# LEDcircuits_PWM.net
KiCad netlist of a schematic drawn in Altium Designer
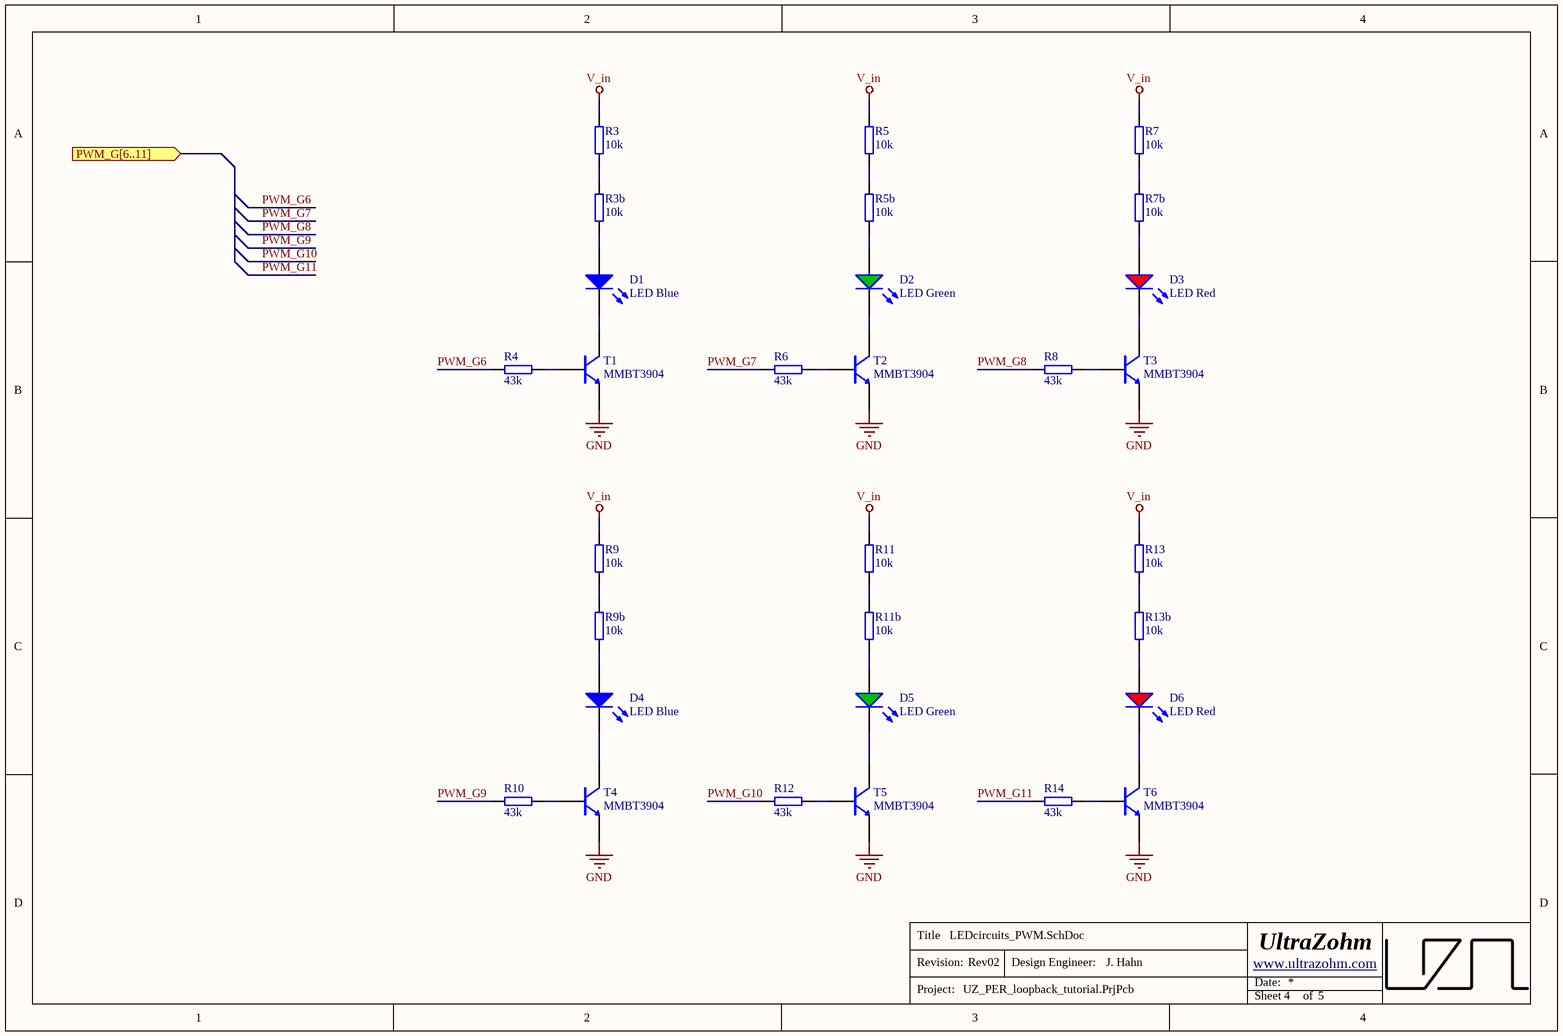
[diagram p0: LEDcircuits_PWM.SchDoc]

(export (version "E")
  (design (tool "Eeschema 10.0.6"))
  (components
    (comp (ref "D1")
      (value "LED Blue")
      (footprint "WL-SMCW_0603")
      (description "Standard LEDs - SMD 0603 blue")
      (fields
        (field (name "MANUFACTURER PART NUMBER") "UZgen_LED_0603_Blue")
        (field (name "MANUFACTURER") "UZgen")
        (field (name "CREATED FROM") "UZgenTool")
      )
      (libsource (lib "user") (part "LED_Blue"))
    )
    (comp (ref "D2")
      (value "LED Green")
      (footprint "WL-SMCW_0603")
      (description "Standard LEDs - SMD 0603 green")
      (fields
        (field (name "MANUFACTURER PART NUMBER") "UZgen_LED_0603_Green")
        (field (name "MANUFACTURER") "UZgen")
        (field (name "CREATED FROM") "UZgenTool")
      )
      (libsource (lib "user") (part "LED_Green"))
    )
    (comp (ref "D3")
      (value "LED Red")
      (footprint "WL-SMCW_0603")
      (description "Standard LEDs - SMD 0603 red")
      (fields
        (field (name "MANUFACTURER PART NUMBER") "UZgen_LED_0603_Red")
        (field (name "MANUFACTURER") "UZgen")
        (field (name "CREATED FROM") "UZgenTool")
      )
      (libsource (lib "user") (part "LED_Red"))
    )
    (comp (ref "D4")
      (value "LED Blue")
      (footprint "WL-SMCW_0603")
      (description "Standard LEDs - SMD 0603 blue")
      (fields
        (field (name "MANUFACTURER PART NUMBER") "UZgen_LED_0603_Blue")
        (field (name "MANUFACTURER") "UZgen")
        (field (name "CREATED FROM") "UZgenTool")
      )
      (libsource (lib "user") (part "LED_Blue"))
    )
    (comp (ref "D5")
      (value "LED Green")
      (footprint "WL-SMCW_0603")
      (description "Standard LEDs - SMD 0603 green")
      (fields
        (field (name "MANUFACTURER PART NUMBER") "UZgen_LED_0603_Green")
        (field (name "MANUFACTURER") "UZgen")
        (field (name "CREATED FROM") "UZgenTool")
      )
      (libsource (lib "user") (part "LED_Green"))
    )
    (comp (ref "D6")
      (value "LED Red")
      (footprint "WL-SMCW_0603")
      (description "Standard LEDs - SMD 0603 red")
      (fields
        (field (name "MANUFACTURER PART NUMBER") "UZgen_LED_0603_Red")
        (field (name "MANUFACTURER") "UZgen")
        (field (name "CREATED FROM") "UZgenTool")
      )
      (libsource (lib "user") (part "LED_Red"))
    )
    (comp (ref "R3")
      (value "10k")
      (footprint "RES 0603_1608")
      (description "SMD resistor 0.1%, 10ppm")
      (fields
        (field (name "MANUFACTURER PART NUMBER") "RQ73C1J10KBTD")
        (field (name "MANUFACTURER") "TE Connectivity")
        (field (name "CREATED FROM") "DHufnagel")
      )
      (libsource (lib "user") (part "Resistor"))
    )
    (comp (ref "R3b")
      (value "10k")
      (footprint "RES 0603_1608")
      (description "SMD resistor 0.1%, 10ppm")
      (fields
        (field (name "MANUFACTURER PART NUMBER") "RQ73C1J10KBTD")
        (field (name "MANUFACTURER") "TE Connectivity")
        (field (name "CREATED FROM") "DHufnagel")
      )
      (libsource (lib "user") (part "Resistor"))
    )
    (comp (ref "R4")
      (value "43k")
      (footprint "RES 0603_1608")
      (description "SMD resistor E24 series")
      (fields
        (field (name "MANUFACTURER PART NUMBER") "RK73B1JTTD433J")
        (field (name "MANUFACTURER") "KOA Speer")
        (field (name "CREATED FROM") "MGremer")
      )
      (libsource (lib "user") (part "Resistor"))
    )
    (comp (ref "R5")
      (value "10k")
      (footprint "RES 0603_1608")
      (description "SMD resistor 0.1%, 10ppm")
      (fields
        (field (name "MANUFACTURER PART NUMBER") "RQ73C1J10KBTD")
        (field (name "MANUFACTURER") "TE Connectivity")
        (field (name "CREATED FROM") "DHufnagel")
      )
      (libsource (lib "user") (part "Resistor"))
    )
    (comp (ref "R5b")
      (value "10k")
      (footprint "RES 0603_1608")
      (description "SMD resistor 0.1%, 10ppm")
      (fields
        (field (name "MANUFACTURER PART NUMBER") "RQ73C1J10KBTD")
        (field (name "MANUFACTURER") "TE Connectivity")
        (field (name "CREATED FROM") "DHufnagel")
      )
      (libsource (lib "user") (part "Resistor"))
    )
    (comp (ref "R6")
      (value "43k")
      (footprint "RES 0603_1608")
      (description "SMD resistor E24 series")
      (fields
        (field (name "MANUFACTURER PART NUMBER") "RK73B1JTTD433J")
        (field (name "MANUFACTURER") "KOA Speer")
        (field (name "CREATED FROM") "MGremer")
      )
      (libsource (lib "user") (part "Resistor"))
    )
    (comp (ref "R7")
      (value "10k")
      (footprint "RES 0603_1608")
      (description "SMD resistor 0.1%, 10ppm")
      (fields
        (field (name "MANUFACTURER PART NUMBER") "RQ73C1J10KBTD")
        (field (name "MANUFACTURER") "TE Connectivity")
        (field (name "CREATED FROM") "DHufnagel")
      )
      (libsource (lib "user") (part "Resistor"))
    )
    (comp (ref "R7b")
      (value "10k")
      (footprint "RES 0603_1608")
      (description "SMD resistor 0.1%, 10ppm")
      (fields
        (field (name "MANUFACTURER PART NUMBER") "RQ73C1J10KBTD")
        (field (name "MANUFACTURER") "TE Connectivity")
        (field (name "CREATED FROM") "DHufnagel")
      )
      (libsource (lib "user") (part "Resistor"))
    )
    (comp (ref "R8")
      (value "43k")
      (footprint "RES 0603_1608")
      (description "SMD resistor E24 series")
      (fields
        (field (name "MANUFACTURER PART NUMBER") "RK73B1JTTD433J")
        (field (name "MANUFACTURER") "KOA Speer")
        (field (name "CREATED FROM") "MGremer")
      )
      (libsource (lib "user") (part "Resistor"))
    )
    (comp (ref "R9")
      (value "10k")
      (footprint "RES 0603_1608")
      (description "SMD resistor 0.1%, 10ppm")
      (fields
        (field (name "MANUFACTURER PART NUMBER") "RQ73C1J10KBTD")
        (field (name "MANUFACTURER") "TE Connectivity")
        (field (name "CREATED FROM") "DHufnagel")
      )
      (libsource (lib "user") (part "Resistor"))
    )
    (comp (ref "R9b")
      (value "10k")
      (footprint "RES 0603_1608")
      (description "SMD resistor 0.1%, 10ppm")
      (fields
        (field (name "MANUFACTURER PART NUMBER") "RQ73C1J10KBTD")
        (field (name "MANUFACTURER") "TE Connectivity")
        (field (name "CREATED FROM") "DHufnagel")
      )
      (libsource (lib "user") (part "Resistor"))
    )
    (comp (ref "R10")
      (value "43k")
      (footprint "RES 0603_1608")
      (description "SMD resistor E24 series")
      (fields
        (field (name "MANUFACTURER PART NUMBER") "RK73B1JTTD433J")
        (field (name "MANUFACTURER") "KOA Speer")
        (field (name "CREATED FROM") "MGremer")
      )
      (libsource (lib "user") (part "Resistor"))
    )
    (comp (ref "R11")
      (value "10k")
      (footprint "RES 0603_1608")
      (description "SMD resistor 0.1%, 10ppm")
      (fields
        (field (name "MANUFACTURER PART NUMBER") "RQ73C1J10KBTD")
        (field (name "MANUFACTURER") "TE Connectivity")
        (field (name "CREATED FROM") "DHufnagel")
      )
      (libsource (lib "user") (part "Resistor"))
    )
    (comp (ref "R11b")
      (value "10k")
      (footprint "RES 0603_1608")
      (description "SMD resistor 0.1%, 10ppm")
      (fields
        (field (name "MANUFACTURER PART NUMBER") "RQ73C1J10KBTD")
        (field (name "MANUFACTURER") "TE Connectivity")
        (field (name "CREATED FROM") "DHufnagel")
      )
      (libsource (lib "user") (part "Resistor"))
    )
    (comp (ref "R12")
      (value "43k")
      (footprint "RES 0603_1608")
      (description "SMD resistor E24 series")
      (fields
        (field (name "MANUFACTURER PART NUMBER") "RK73B1JTTD433J")
        (field (name "MANUFACTURER") "KOA Speer")
        (field (name "CREATED FROM") "MGremer")
      )
      (libsource (lib "user") (part "Resistor"))
    )
    (comp (ref "R13")
      (value "10k")
      (footprint "RES 0603_1608")
      (description "SMD resistor 0.1%, 10ppm")
      (fields
        (field (name "MANUFACTURER PART NUMBER") "RQ73C1J10KBTD")
        (field (name "MANUFACTURER") "TE Connectivity")
        (field (name "CREATED FROM") "DHufnagel")
      )
      (libsource (lib "user") (part "Resistor"))
    )
    (comp (ref "R13b")
      (value "10k")
      (footprint "RES 0603_1608")
      (description "SMD resistor 0.1%, 10ppm")
      (fields
        (field (name "MANUFACTURER PART NUMBER") "RQ73C1J10KBTD")
        (field (name "MANUFACTURER") "TE Connectivity")
        (field (name "CREATED FROM") "DHufnagel")
      )
      (libsource (lib "user") (part "Resistor"))
    )
    (comp (ref "R14")
      (value "43k")
      (footprint "RES 0603_1608")
      (description "SMD resistor E24 series")
      (fields
        (field (name "MANUFACTURER PART NUMBER") "RK73B1JTTD433J")
        (field (name "MANUFACTURER") "KOA Speer")
        (field (name "CREATED FROM") "MGremer")
      )
      (libsource (lib "user") (part "Resistor"))
    )
    (comp (ref "T1")
      (value "MMBT3904")
      (footprint "SOT95P280X145-3N")
      (fields
        (field (name "MANUFACTURER") "Jiangsu Changjing Electronics Technology Co., Ltd.")
        (field (name "LCSC PART NUMBER") "C20526")
        (field (name "CREATED FROM") "NDiringer")
      )
      (libsource (lib "user") (part "NPN-SOT23"))
    )
    (comp (ref "T2")
      (value "MMBT3904")
      (footprint "SOT95P280X145-3N")
      (fields
        (field (name "MANUFACTURER") "Jiangsu Changjing Electronics Technology Co., Ltd.")
        (field (name "LCSC PART NUMBER") "C20526")
        (field (name "CREATED FROM") "NDiringer")
      )
      (libsource (lib "user") (part "NPN-SOT23"))
    )
    (comp (ref "T3")
      (value "MMBT3904")
      (footprint "SOT95P280X145-3N")
      (fields
        (field (name "MANUFACTURER") "Jiangsu Changjing Electronics Technology Co., Ltd.")
        (field (name "LCSC PART NUMBER") "C20526")
        (field (name "CREATED FROM") "NDiringer")
      )
      (libsource (lib "user") (part "NPN-SOT23"))
    )
    (comp (ref "T4")
      (value "MMBT3904")
      (footprint "SOT95P280X145-3N")
      (fields
        (field (name "MANUFACTURER") "Jiangsu Changjing Electronics Technology Co., Ltd.")
        (field (name "LCSC PART NUMBER") "C20526")
        (field (name "CREATED FROM") "NDiringer")
      )
      (libsource (lib "user") (part "NPN-SOT23"))
    )
    (comp (ref "T5")
      (value "MMBT3904")
      (footprint "SOT95P280X145-3N")
      (fields
        (field (name "MANUFACTURER") "Jiangsu Changjing Electronics Technology Co., Ltd.")
        (field (name "LCSC PART NUMBER") "C20526")
        (field (name "CREATED FROM") "NDiringer")
      )
      (libsource (lib "user") (part "NPN-SOT23"))
    )
    (comp (ref "T6")
      (value "MMBT3904")
      (footprint "SOT95P280X145-3N")
      (fields
        (field (name "MANUFACTURER") "Jiangsu Changjing Electronics Technology Co., Ltd.")
        (field (name "LCSC PART NUMBER") "C20526")
        (field (name "CREATED FROM") "NDiringer")
      )
      (libsource (lib "user") (part "NPN-SOT23"))
    )
  )
  (nets
    (net (code "1") (name "/PWM_G6") (class "Default")
      (node (ref "R4") (pin "1") (pinfunction "1_1") (pintype "passive"))
    )
    (net (code "2") (name "/PWM_G7") (class "Default")
      (node (ref "R6") (pin "1") (pinfunction "1_1") (pintype "passive"))
    )
    (net (code "3") (name "/PWM_G8") (class "Default")
      (node (ref "R8") (pin "1") (pinfunction "1_1") (pintype "passive"))
    )
    (net (code "4") (name "/PWM_G9") (class "Default")
      (node (ref "R10") (pin "1") (pinfunction "1_1") (pintype "passive"))
    )
    (net (code "5") (name "/PWM_G10") (class "Default")
      (node (ref "R12") (pin "1") (pinfunction "1_1") (pintype "passive"))
    )
    (net (code "6") (name "/PWM_G11") (class "Default")
      (node (ref "R14") (pin "1") (pinfunction "1_1") (pintype "passive"))
    )
    (net (code "8") (name "GND") (class "Default")
      (node (ref "T1") (pin "2") (pinfunction "EMITTER_2") (pintype "passive"))
      (node (ref "T2") (pin "2") (pinfunction "EMITTER_2") (pintype "passive"))
      (node (ref "T3") (pin "2") (pinfunction "EMITTER_2") (pintype "passive"))
      (node (ref "T4") (pin "2") (pinfunction "EMITTER_2") (pintype "passive"))
      (node (ref "T5") (pin "2") (pinfunction "EMITTER_2") (pintype "passive"))
      (node (ref "T6") (pin "2") (pinfunction "EMITTER_2") (pintype "passive"))
    )
    (net (code "9") (name "Net-(D1-A)") (class "Default")
      (node (ref "D1") (pin "2") (pinfunction "A_2") (pintype "passive"))
      (node (ref "R3b") (pin "1") (pinfunction "1_1") (pintype "passive"))
    )
    (net (code "10") (name "Net-(D1-K)") (class "Default")
      (node (ref "D1") (pin "1") (pinfunction "K_1") (pintype "passive"))
      (node (ref "T1") (pin "3") (pinfunction "COLLECTOR_3") (pintype "passive"))
    )
    (net (code "11") (name "Net-(D2-A)") (class "Default")
      (node (ref "D2") (pin "2") (pinfunction "A_2") (pintype "passive"))
      (node (ref "R5b") (pin "1") (pinfunction "1_1") (pintype "passive"))
    )
    (net (code "12") (name "Net-(D2-K)") (class "Default")
      (node (ref "D2") (pin "1") (pinfunction "K_1") (pintype "passive"))
      (node (ref "T2") (pin "3") (pinfunction "COLLECTOR_3") (pintype "passive"))
    )
    (net (code "13") (name "Net-(D3-A)") (class "Default")
      (node (ref "D3") (pin "2") (pinfunction "A_2") (pintype "passive"))
      (node (ref "R7b") (pin "1") (pinfunction "1_1") (pintype "passive"))
    )
    (net (code "14") (name "Net-(D3-K)") (class "Default")
      (node (ref "D3") (pin "1") (pinfunction "K_1") (pintype "passive"))
      (node (ref "T3") (pin "3") (pinfunction "COLLECTOR_3") (pintype "passive"))
    )
    (net (code "15") (name "Net-(D4-A)") (class "Default")
      (node (ref "D4") (pin "2") (pinfunction "A_2") (pintype "passive"))
      (node (ref "R9b") (pin "1") (pinfunction "1_1") (pintype "passive"))
    )
    (net (code "16") (name "Net-(D4-K)") (class "Default")
      (node (ref "D4") (pin "1") (pinfunction "K_1") (pintype "passive"))
      (node (ref "T4") (pin "3") (pinfunction "COLLECTOR_3") (pintype "passive"))
    )
    (net (code "17") (name "Net-(D5-A)") (class "Default")
      (node (ref "D5") (pin "2") (pinfunction "A_2") (pintype "passive"))
      (node (ref "R11b") (pin "1") (pinfunction "1_1") (pintype "passive"))
    )
    (net (code "18") (name "Net-(D5-K)") (class "Default")
      (node (ref "D5") (pin "1") (pinfunction "K_1") (pintype "passive"))
      (node (ref "T5") (pin "3") (pinfunction "COLLECTOR_3") (pintype "passive"))
    )
    (net (code "19") (name "Net-(D6-A)") (class "Default")
      (node (ref "D6") (pin "2") (pinfunction "A_2") (pintype "passive"))
      (node (ref "R13b") (pin "1") (pinfunction "1_1") (pintype "passive"))
    )
    (net (code "20") (name "Net-(D6-K)") (class "Default")
      (node (ref "D6") (pin "1") (pinfunction "K_1") (pintype "passive"))
      (node (ref "T6") (pin "3") (pinfunction "COLLECTOR_3") (pintype "passive"))
    )
    (net (code "21") (name "Net-(R3-Pad1)") (class "Default")
      (node (ref "R3") (pin "1") (pinfunction "1_1") (pintype "passive"))
      (node (ref "R3b") (pin "2") (pinfunction "2_2") (pintype "passive"))
    )
    (net (code "22") (name "Net-(R5-Pad1)") (class "Default")
      (node (ref "R5") (pin "1") (pinfunction "1_1") (pintype "passive"))
      (node (ref "R5b") (pin "2") (pinfunction "2_2") (pintype "passive"))
    )
    (net (code "23") (name "Net-(R7-Pad1)") (class "Default")
      (node (ref "R7") (pin "1") (pinfunction "1_1") (pintype "passive"))
      (node (ref "R7b") (pin "2") (pinfunction "2_2") (pintype "passive"))
    )
    (net (code "24") (name "Net-(R9-Pad1)") (class "Default")
      (node (ref "R9") (pin "1") (pinfunction "1_1") (pintype "passive"))
      (node (ref "R9b") (pin "2") (pinfunction "2_2") (pintype "passive"))
    )
    (net (code "25") (name "Net-(R11-Pad1)") (class "Default")
      (node (ref "R11") (pin "1") (pinfunction "1_1") (pintype "passive"))
      (node (ref "R11b") (pin "2") (pinfunction "2_2") (pintype "passive"))
    )
    (net (code "26") (name "Net-(R13-Pad1)") (class "Default")
      (node (ref "R13") (pin "1") (pinfunction "1_1") (pintype "passive"))
      (node (ref "R13b") (pin "2") (pinfunction "2_2") (pintype "passive"))
    )
    (net (code "27") (name "Net-(T1-BASIS)") (class "Default")
      (node (ref "R4") (pin "2") (pinfunction "2_2") (pintype "passive"))
      (node (ref "T1") (pin "1") (pinfunction "BASIS_1") (pintype "passive"))
    )
    (net (code "28") (name "Net-(T2-BASIS)") (class "Default")
      (node (ref "R6") (pin "2") (pinfunction "2_2") (pintype "passive"))
      (node (ref "T2") (pin "1") (pinfunction "BASIS_1") (pintype "passive"))
    )
    (net (code "29") (name "Net-(T3-BASIS)") (class "Default")
      (node (ref "R8") (pin "2") (pinfunction "2_2") (pintype "passive"))
      (node (ref "T3") (pin "1") (pinfunction "BASIS_1") (pintype "passive"))
    )
    (net (code "30") (name "Net-(T4-BASIS)") (class "Default")
      (node (ref "R10") (pin "2") (pinfunction "2_2") (pintype "passive"))
      (node (ref "T4") (pin "1") (pinfunction "BASIS_1") (pintype "passive"))
    )
    (net (code "31") (name "Net-(T5-BASIS)") (class "Default")
      (node (ref "R12") (pin "2") (pinfunction "2_2") (pintype "passive"))
      (node (ref "T5") (pin "1") (pinfunction "BASIS_1") (pintype "passive"))
    )
    (net (code "32") (name "Net-(T6-BASIS)") (class "Default")
      (node (ref "R14") (pin "2") (pinfunction "2_2") (pintype "passive"))
      (node (ref "T6") (pin "1") (pinfunction "BASIS_1") (pintype "passive"))
    )
    (net (code "33") (name "V_in") (class "Default")
      (node (ref "R11") (pin "2") (pinfunction "2_2") (pintype "passive"))
      (node (ref "R13") (pin "2") (pinfunction "2_2") (pintype "passive"))
      (node (ref "R3") (pin "2") (pinfunction "2_2") (pintype "passive"))
      (node (ref "R5") (pin "2") (pinfunction "2_2") (pintype "passive"))
      (node (ref "R7") (pin "2") (pinfunction "2_2") (pintype "passive"))
      (node (ref "R9") (pin "2") (pinfunction "2_2") (pintype "passive"))
    )
  )
)
